# reciever_pcb.net
KiCad netlist of a schematic drawn in EAGLE
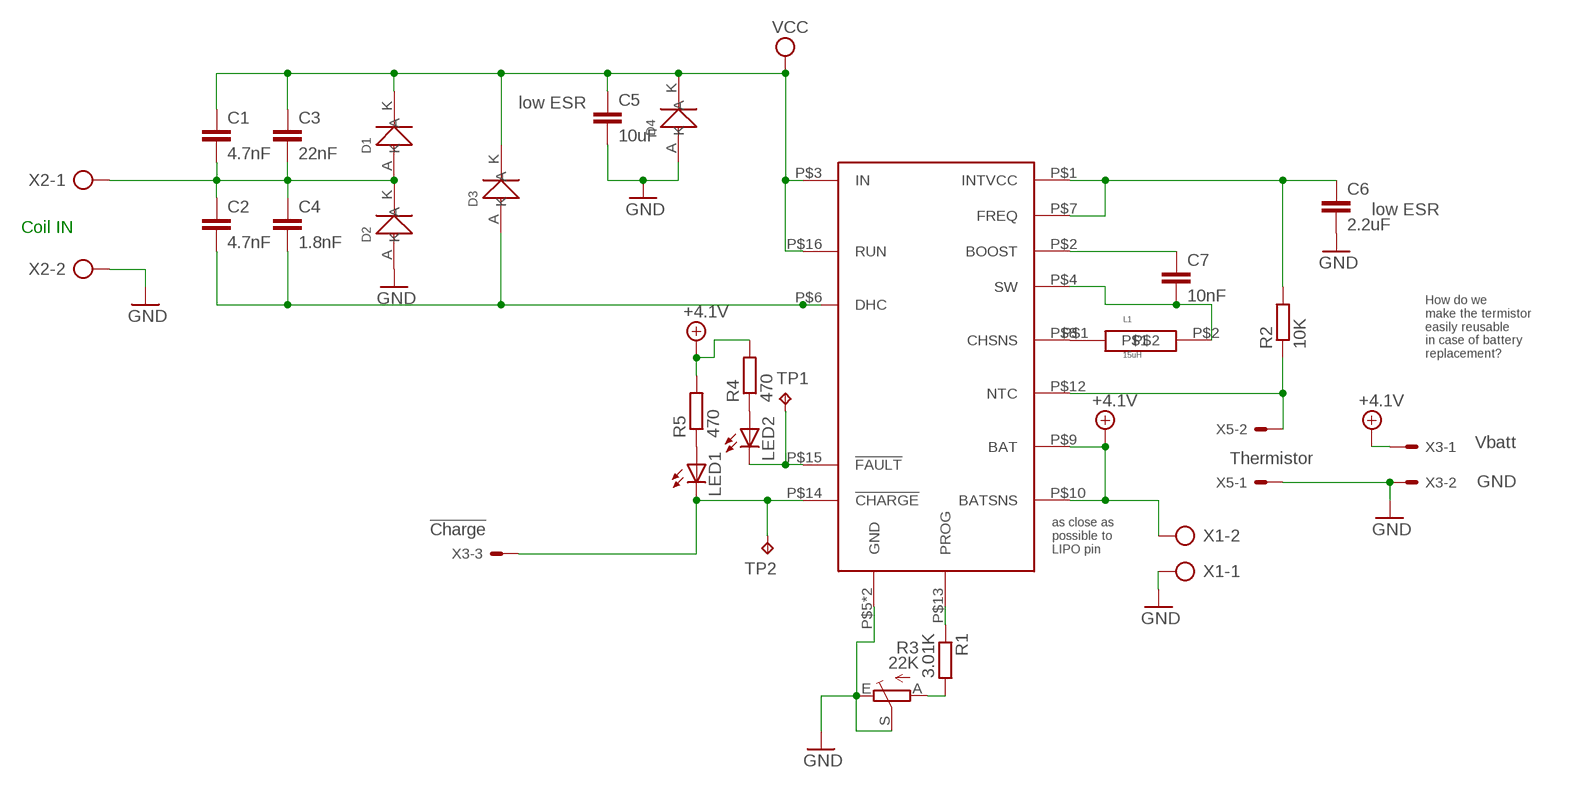
[diagram p0: schematic, sheet 1]

(export (version "E")
  (design (tool "Eeschema 10.0.6"))
  (components
    (comp (ref "C1")
      (value "4.7nF")
      (footprint "eagle-import:C0805")
      (libsource (lib "eagle-import") (part "C-EUC0805"))
    )
    (comp (ref "C2")
      (value "4.7nF")
      (footprint "eagle-import:C0805")
      (libsource (lib "eagle-import") (part "C-EUC0805"))
    )
    (comp (ref "C3")
      (value "22nF")
      (footprint "eagle-import:C0805")
      (libsource (lib "eagle-import") (part "C-EUC0805"))
    )
    (comp (ref "C4")
      (value "1.8nF")
      (footprint "eagle-import:C0805")
      (libsource (lib "eagle-import") (part "C-EUC0805"))
    )
    (comp (ref "C5")
      (value "10uF")
      (footprint "eagle-import:C0805")
      (libsource (lib "eagle-import") (part "C-EUC0805"))
    )
    (comp (ref "C6")
      (value "2.2uF")
      (footprint "eagle-import:C0805")
      (libsource (lib "eagle-import") (part "C-EUC0805"))
    )
    (comp (ref "C7")
      (value "10nF")
      (footprint "eagle-import:C0805")
      (libsource (lib "eagle-import") (part "C-EUC0805"))
    )
    (comp (ref "D1")
      (value "DFLS240L")
      (footprint "eagle-import:POWERDI123")
      (libsource (lib "eagle-import") (part "DFLS240L"))
    )
    (comp (ref "D2")
      (value "DFLS240L")
      (footprint "eagle-import:POWERDI123")
      (libsource (lib "eagle-import") (part "DFLS240L"))
    )
    (comp (ref "D3")
      (value "DFLS240L")
      (footprint "eagle-import:POWERDI123")
      (libsource (lib "eagle-import") (part "DFLS240L"))
    )
    (comp (ref "D4")
      (value "39VZ")
      (footprint "eagle-import:POWERDI123")
      (libsource (lib "eagle-import") (part "DFLS240L"))
    )
    (comp (ref "L1")
      (value "15uH")
      (footprint "eagle-import:D62LCB")
      (libsource (lib "eagle-import") (part "D62LCB"))
    )
    (comp (ref "LED1")
      (value "LEDCHIP-LED0805")
      (footprint "eagle-import:CHIP-LED0805")
      (libsource (lib "eagle-import") (part "LEDCHIP-LED0805"))
    )
    (comp (ref "LED2")
      (value "LEDCHIP-LED0805")
      (footprint "eagle-import:CHIP-LED0805")
      (libsource (lib "eagle-import") (part "LEDCHIP-LED0805"))
    )
    (comp (ref "R1")
      (value "3.01K")
      (footprint "eagle-import:R0805")
      (libsource (lib "eagle-import") (part "R-EU_R0805"))
    )
    (comp (ref "R2")
      (value "10K")
      (footprint "eagle-import:R0805")
      (libsource (lib "eagle-import") (part "R-EU_R0805"))
    )
    (comp (ref "R3")
      (value "22K")
      (footprint "eagle-import:S63S")
      (libsource (lib "eagle-import") (part "TRIM_EU-S63S"))
    )
    (comp (ref "R4")
      (value "470")
      (footprint "eagle-import:R0805")
      (libsource (lib "eagle-import") (part "R-EU_R0805"))
    )
    (comp (ref "R5")
      (value "470")
      (footprint "eagle-import:R0805")
      (libsource (lib "eagle-import") (part "R-EU_R0805"))
    )
    (comp (ref "TP1")
      (value "TPTP19R")
      (footprint "eagle-import:TP19R")
      (libsource (lib "eagle-import") (part "TPTP19R"))
    )
    (comp (ref "TP2")
      (value "TPTP19R")
      (footprint "eagle-import:TP19R")
      (libsource (lib "eagle-import") (part "TPTP19R"))
    )
    (comp (ref "U$1")
      (value "LT4120")
      (footprint "eagle-import:QFN16")
      (libsource (lib "eagle-import") (part "LT4120"))
    )
    (comp (ref "X1")
      (value "AK500/2")
      (footprint "eagle-import:AK500_2")
      (libsource (lib "eagle-import") (part "AK500/2"))
    )
    (comp (ref "X2")
      (value "AK500/2")
      (footprint "eagle-import:AK500_2")
      (libsource (lib "eagle-import") (part "AK500/2"))
    )
    (comp (ref "X3")
      (value "KK-156-3")
      (footprint "eagle-import:KK-156-3")
      (libsource (lib "eagle-import") (part "KK-156-3"))
    )
    (comp (ref "X5")
      (value "KK-156-2")
      (footprint "eagle-import:KK-156-2")
      (libsource (lib "eagle-import") (part "KK-156-2"))
    )
  )
  (nets
    (net (code "1") (name "+4.1V") (class "Default")
      (node (ref "R4") (pin "2") (pinfunction "2_2") (pintype "passive"))
      (node (ref "R5") (pin "2") (pinfunction "2_2") (pintype "passive"))
      (node (ref "U$1") (pin "P$10") (pinfunction "BATSNS_P$10") (pintype "bidirectional"))
      (node (ref "U$1") (pin "P$9") (pinfunction "BAT_P$9") (pintype "bidirectional"))
      (node (ref "X1") (pin "2") (pinfunction "KL_2") (pintype "passive"))
      (node (ref "X3") (pin "1") (pinfunction "S_1") (pintype "passive"))
    )
    (net (code "2") (name "GND") (class "Default")
      (node (ref "C5") (pin "2") (pinfunction "2_2") (pintype "passive"))
      (node (ref "C6") (pin "2") (pinfunction "2_2") (pintype "passive"))
      (node (ref "D2") (pin "A") (pinfunction "A_A") (pintype "bidirectional"))
      (node (ref "D4") (pin "A") (pinfunction "A_A") (pintype "bidirectional"))
      (node (ref "R3") (pin "E") (pinfunction "E_E") (pintype "passive"))
      (node (ref "R3") (pin "S") (pinfunction "S_S") (pintype "passive"))
      (node (ref "U$1") (pin "P$17") (pinfunction "GND_P$17") (pintype "power_in"))
      (node (ref "U$1") (pin "P$5") (pinfunction "GND_P$5") (pintype "power_in"))
      (node (ref "X1") (pin "1") (pinfunction "KL_1") (pintype "passive"))
      (node (ref "X2") (pin "2") (pinfunction "KL_2") (pintype "passive"))
      (node (ref "X3") (pin "2") (pinfunction "S_2") (pintype "passive"))
      (node (ref "X5") (pin "1") (pinfunction "S_1") (pintype "passive"))
    )
    (net (code "3") (name "Net-(LED1-PadA)") (class "Default")
      (node (ref "LED1") (pin "A") (pinfunction "A_A") (pintype "passive"))
      (node (ref "R5") (pin "1") (pinfunction "1_1") (pintype "passive"))
    )
    (net (code "4") (name "Net-(LED2-PadA)") (class "Default")
      (node (ref "LED2") (pin "A") (pinfunction "A_A") (pintype "passive"))
      (node (ref "R4") (pin "1") (pinfunction "1_1") (pintype "passive"))
    )
    (net (code "5") (name "Net-(R1-Pad2)") (class "Default")
      (node (ref "R1") (pin "2") (pinfunction "2_2") (pintype "passive"))
      (node (ref "R3") (pin "A") (pinfunction "A_A") (pintype "passive"))
    )
    (net (code "6") (name "Net-(U$1-BOOST)") (class "Default")
      (node (ref "C7") (pin "1") (pinfunction "1_1") (pintype "passive"))
      (node (ref "U$1") (pin "P$2") (pinfunction "BOOST_P$2") (pintype "bidirectional"))
    )
    (net (code "7") (name "Net-(U$1-CHSNS)") (class "Default")
      (node (ref "L1") (pin "P$1") (pinfunction "P$1_P$1") (pintype "bidirectional"))
      (node (ref "U$1") (pin "P$8") (pinfunction "CHSNS_P$8") (pintype "bidirectional"))
    )
    (net (code "8") (name "Net-(U$1-DHC)") (class "Default")
      (node (ref "C2") (pin "2") (pinfunction "2_2") (pintype "passive"))
      (node (ref "C4") (pin "2") (pinfunction "2_2") (pintype "passive"))
      (node (ref "D3") (pin "A") (pinfunction "A_A") (pintype "bidirectional"))
      (node (ref "U$1") (pin "P$6") (pinfunction "DHC_P$6") (pintype "bidirectional"))
    )
    (net (code "9") (name "Net-(U$1-FREQ)") (class "Default")
      (node (ref "C6") (pin "1") (pinfunction "1_1") (pintype "passive"))
      (node (ref "R2") (pin "2") (pinfunction "2_2") (pintype "passive"))
      (node (ref "U$1") (pin "P$1") (pinfunction "INTVCC_P$1") (pintype "bidirectional"))
      (node (ref "U$1") (pin "P$7") (pinfunction "FREQ_P$7") (pintype "bidirectional"))
    )
    (net (code "10") (name "Net-(U$1-NTC)") (class "Default")
      (node (ref "R2") (pin "1") (pinfunction "1_1") (pintype "passive"))
      (node (ref "U$1") (pin "P$12") (pinfunction "NTC_P$12") (pintype "bidirectional"))
      (node (ref "X5") (pin "2") (pinfunction "S_2") (pintype "passive"))
    )
    (net (code "11") (name "Net-(U$1-PROG)") (class "Default")
      (node (ref "R1") (pin "1") (pinfunction "1_1") (pintype "passive"))
      (node (ref "U$1") (pin "P$13") (pinfunction "PROG_P$13") (pintype "bidirectional"))
    )
    (net (code "12") (name "Net-(U$1-SW)") (class "Default")
      (node (ref "C7") (pin "2") (pinfunction "2_2") (pintype "passive"))
      (node (ref "L1") (pin "P$2") (pinfunction "P$2_P$2") (pintype "bidirectional"))
      (node (ref "U$1") (pin "P$4") (pinfunction "SW_P$4") (pintype "bidirectional"))
    )
    (net (code "13") (name "Net-(U$1-~{CHARGE})") (class "Default")
      (node (ref "LED1") (pin "C") (pinfunction "C_C") (pintype "passive"))
      (node (ref "TP2") (pin "TP") (pinfunction "TP_TP") (pintype "input"))
      (node (ref "U$1") (pin "P$14") (pinfunction "~{CHARGE}_P$14") (pintype "bidirectional"))
      (node (ref "X3") (pin "3") (pinfunction "S_3") (pintype "passive"))
    )
    (net (code "14") (name "Net-(U$1-~{FAULT})") (class "Default")
      (node (ref "LED2") (pin "C") (pinfunction "C_C") (pintype "passive"))
      (node (ref "TP1") (pin "TP") (pinfunction "TP_TP") (pintype "input"))
      (node (ref "U$1") (pin "P$15") (pinfunction "~{FAULT}_P$15") (pintype "bidirectional"))
    )
    (net (code "15") (name "Net-(X2A-KL)") (class "Default")
      (node (ref "C1") (pin "2") (pinfunction "2_2") (pintype "passive"))
      (node (ref "C2") (pin "1") (pinfunction "1_1") (pintype "passive"))
      (node (ref "C3") (pin "2") (pinfunction "2_2") (pintype "passive"))
      (node (ref "C4") (pin "1") (pinfunction "1_1") (pintype "passive"))
      (node (ref "D1") (pin "A") (pinfunction "A_A") (pintype "bidirectional"))
      (node (ref "D2") (pin "K") (pinfunction "K_K") (pintype "bidirectional"))
      (node (ref "X2") (pin "1") (pinfunction "KL_1") (pintype "passive"))
    )
    (net (code "16") (name "VCC") (class "Default")
      (node (ref "C1") (pin "1") (pinfunction "1_1") (pintype "passive"))
      (node (ref "C3") (pin "1") (pinfunction "1_1") (pintype "passive"))
      (node (ref "C5") (pin "1") (pinfunction "1_1") (pintype "passive"))
      (node (ref "D1") (pin "K") (pinfunction "K_K") (pintype "bidirectional"))
      (node (ref "D3") (pin "K") (pinfunction "K_K") (pintype "bidirectional"))
      (node (ref "D4") (pin "K") (pinfunction "K_K") (pintype "bidirectional"))
      (node (ref "U$1") (pin "P$16") (pinfunction "RUN_P$16") (pintype "bidirectional"))
      (node (ref "U$1") (pin "P$3") (pinfunction "IN_P$3") (pintype "power_in"))
    )
  )
)
